# Transconductance.net
KiCad netlist of a schematic drawn in Altium Designer
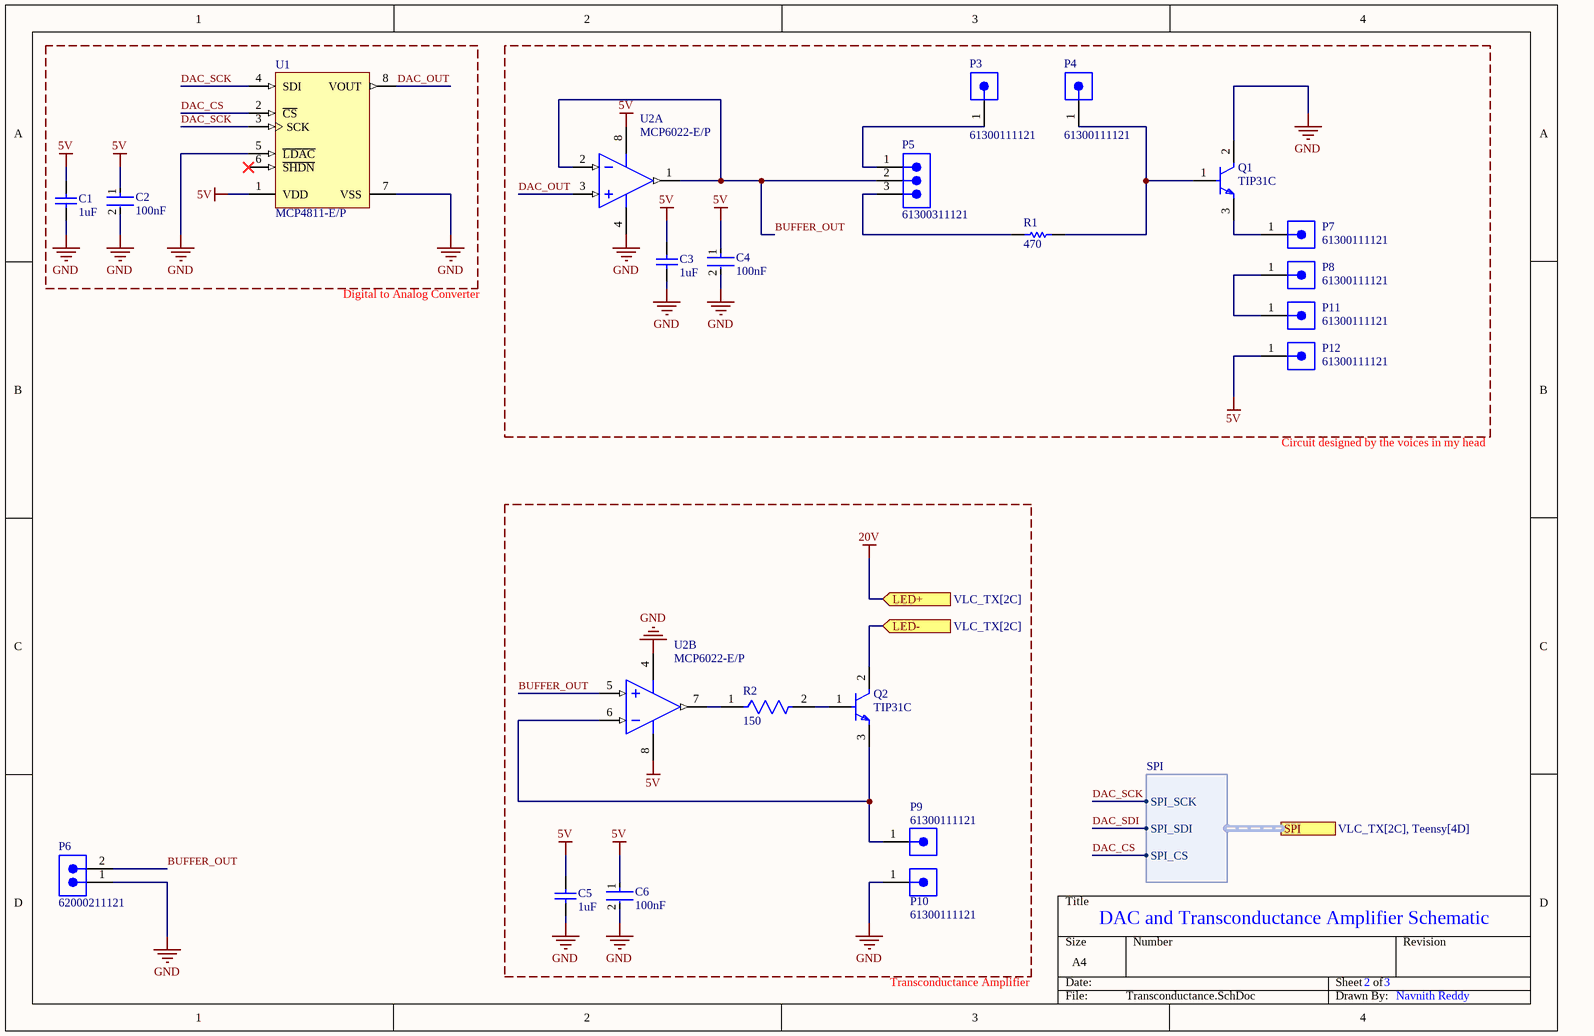
[diagram p0: Transconductance.SchDoc]

(export (version "E")
  (design (tool "Eeschema 10.0.6"))
  (components
    (comp (ref "C1")
      (value "1uF")
      (footprint "CAPC2013X145X50LL20T25")
      (fields (field (name "MANUFACTURER") "Kemet") (field (name "PART NUMBER") "C0805C105K4PACTU"))
      (libsource (lib "Altium Content Vault") (part "CAP"))
    )
    (comp (ref "C2")
      (value "100nF")
      (footprint "FP-C0805C-DN-MFG")
      (description "CAP CER 0.1UF 16V X7R 0805")
      (fields
        (field (name "OCTOPART") "https://octopart.com/c0805c104k4ractu-kemet-92155")
        (field (name "TOLERANCE") "0.1")
      )
      (libsource (lib "Altium Content Vault") (part "b4654b650e69147ec39a6b967a45e02"))
    )
    (comp (ref "C3")
      (value "1uF")
      (footprint "CAPC2013X145X50LL20T25")
      (fields (field (name "MANUFACTURER") "Kemet") (field (name "PART NUMBER") "C0805C105K4PACTU"))
      (libsource (lib "Altium Content Vault") (part "CAP"))
    )
    (comp (ref "C4")
      (value "100nF")
      (footprint "FP-C0805C-DN-MFG")
      (description "CAP CER 0.1UF 16V X7R 0805")
      (fields
        (field (name "OCTOPART") "https://octopart.com/c0805c104k4ractu-kemet-92155")
        (field (name "TOLERANCE") "0.1")
      )
      (libsource (lib "Altium Content Vault") (part "b4654b650e69147ec39a6b967a45e02"))
    )
    (comp (ref "C5")
      (value "1uF")
      (footprint "CAPC2013X145X50LL20T25")
      (fields (field (name "MANUFACTURER") "Kemet") (field (name "PART NUMBER") "C0805C105K4PACTU"))
      (libsource (lib "Altium Content Vault") (part "CAP"))
    )
    (comp (ref "C6")
      (value "100nF")
      (footprint "FP-C0805C-DN-MFG")
      (description "CAP CER 0.1UF 16V X7R 0805")
      (fields
        (field (name "OCTOPART") "https://octopart.com/c0805c104k4ractu-kemet-92155")
        (field (name "TOLERANCE") "0.1")
      )
      (libsource (lib "Altium Content Vault") (part "b4654b650e69147ec39a6b967a45e02"))
    )
    (comp (ref "P3")
      (value "61300111121")
      (footprint "61300111121")
      (libsource (lib "Altium Content Vault") (part "Header_Male_1R_01P"))
    )
    (comp (ref "P4")
      (value "61300111121")
      (footprint "61300111121")
      (libsource (lib "Altium Content Vault") (part "Header_Male_1R_01P"))
    )
    (comp (ref "P5")
      (value "61300311121")
      (footprint "61300311121")
      (libsource (lib "Altium Content Vault") (part "Header_Male_1R_03P"))
    )
    (comp (ref "P6")
      (value "62000211121")
      (footprint "62000211121")
      (libsource (lib "Altium Content Vault") (part "Header_Male_1R_02P"))
    )
    (comp (ref "P7")
      (value "61300111121")
      (footprint "61300111121")
      (libsource (lib "Altium Content Vault") (part "Header_Male_1R_01P"))
    )
    (comp (ref "P8")
      (value "61300111121")
      (footprint "61300111121")
      (libsource (lib "Altium Content Vault") (part "Header_Male_1R_01P"))
    )
    (comp (ref "P9")
      (value "61300111121")
      (footprint "61300111121")
      (libsource (lib "Altium Content Vault") (part "Header_Male_1R_01P"))
    )
    (comp (ref "P10")
      (value "61300111121")
      (footprint "61300111121")
      (libsource (lib "Altium Content Vault") (part "Header_Male_1R_01P"))
    )
    (comp (ref "P11")
      (value "61300111121")
      (footprint "61300111121")
      (libsource (lib "Altium Content Vault") (part "Header_Male_1R_01P"))
    )
    (comp (ref "P12")
      (value "61300111121")
      (footprint "61300111121")
      (libsource (lib "Altium Content Vault") (part "Header_Male_1R_01P"))
    )
    (comp (ref "Q1")
      (value "TIP31C")
      (footprint "FP-TO-220-P0A0015988-MFG")
      (description "TRANS NPN 100V 3A TO-220")
      (fields
        (field (name "OCTOPART") "https://octopart.com/tip31c-stmicroelectronics-15555")
        (field (name "MANUFACTURER") "STMicroelectronics")
      )
      (libsource (lib "Altium Content Vault") (part "1c57d9dae74fe2702546667b0e849db"))
    )
    (comp (ref "Q2")
      (value "TIP31C")
      (footprint "FP-TO-220-P0A0015988-MFG")
      (description "TRANS NPN 100V 3A TO-220")
      (fields
        (field (name "OCTOPART") "https://octopart.com/tip31c-stmicroelectronics-15555")
        (field (name "MANUFACTURER") "STMicroelectronics")
      )
      (libsource (lib "Altium Content Vault") (part "1c57d9dae74fe2702546667b0e849db"))
    )
    (comp (ref "R1")
      (value "470")
      (footprint "RESC2013X50X30LL20T20")
      (fields (field (name "MANUFACTURER") "Vishay Dale") (field (name "PART NUMBER") "CRCW0805470RFKEA"))
      (libsource (lib "Altium Content Vault") (part "RES"))
    )
    (comp (ref "R2")
      (value "150")
      (footprint "FP-CRCW0805-e3-IPC_A")
      (description "RES Thick Film, 150Ω, 5%, 0.125W, 200ppm/°C, 0805")
      (fields (field (name "TOLERANCE") "5%"))
      (libsource (lib "Altium Content Vault") (part "1029c3af85768c4190bb7ad29bc67b5"))
    )
    (comp (ref "U1")
      (value "MCP4811-E/P")
      (footprint "PDIP300-P8")
      (description "10-Bit DACs with Internal VREF and SPI Interface, 8-Pin PDIP, Extended Temperature")
      (libsource (lib "Altium Content Vault") (part "CON-DAC-MCP4821-8"))
    )
    (comp (ref "U2")
      (value "MCP6022-E/P")
      (footprint "PDIP300-P8")
      (description "None")
      (libsource (lib "Altium Content Vault") (part "AMP-OPA-MCP6022-IL8"))
    )
  )
  (nets
    (net (code "2") (name "/BUFFER_OUT") (class "Default")
      (node (ref "P5") (pin "2") (pinfunction "2_2") (pintype "passive"))
      (node (ref "P6") (pin "2") (pinfunction "2_2") (pintype "passive"))
      (node (ref "U2") (pin "1") (pinfunction "VOUTA_1") (pintype "output"))
      (node (ref "U2") (pin "2") (pinfunction "VINA-_2") (pintype "input"))
      (node (ref "U2") (pin "5") (pinfunction "VINB+_5") (pintype "input"))
    )
    (net (code "3") (name "/DAC_CS") (class "Default")
      (node (ref "U1") (pin "2") (pinfunction "~{CS}_2") (pintype "input"))
    )
    (net (code "4") (name "/DAC_OUT") (class "Default")
      (node (ref "U1") (pin "8") (pinfunction "VOUT_8") (pintype "output"))
      (node (ref "U2") (pin "3") (pinfunction "VINA+_3") (pintype "input"))
    )
    (net (code "5") (name "/DAC_SCK") (class "Default")
      (node (ref "U1") (pin "3") (pinfunction "SCK_3") (pintype "input"))
      (node (ref "U1") (pin "4") (pinfunction "SDI_4") (pintype "input"))
    )
    (net (code "7") (name "/LED-") (class "Default")
      (node (ref "Q2") (pin "2") (pinfunction "C_2") (pintype "passive"))
    )
    (net (code "9") (name "5V") (class "Default")
      (node (ref "C1") (pin "2") (pinfunction "2_2") (pintype "passive"))
      (node (ref "C2") (pin "1") (pinfunction "1_1") (pintype "passive"))
      (node (ref "C3") (pin "2") (pinfunction "2_2") (pintype "passive"))
      (node (ref "C4") (pin "1") (pinfunction "1_1") (pintype "passive"))
      (node (ref "C5") (pin "2") (pinfunction "2_2") (pintype "passive"))
      (node (ref "C6") (pin "1") (pinfunction "1_1") (pintype "passive"))
      (node (ref "P12") (pin "1") (pinfunction "1_1") (pintype "passive"))
      (node (ref "U1") (pin "1") (pinfunction "VDD_1") (pintype "power_in"))
      (node (ref "U2") (pin "8") (pinfunction "VDD_8") (pintype "power_in"))
    )
    (net (code "11") (name "GND") (class "Default")
      (node (ref "C1") (pin "1") (pinfunction "1_1") (pintype "passive"))
      (node (ref "C2") (pin "2") (pinfunction "2_2") (pintype "passive"))
      (node (ref "C3") (pin "1") (pinfunction "1_1") (pintype "passive"))
      (node (ref "C4") (pin "2") (pinfunction "2_2") (pintype "passive"))
      (node (ref "C5") (pin "1") (pinfunction "1_1") (pintype "passive"))
      (node (ref "C6") (pin "2") (pinfunction "2_2") (pintype "passive"))
      (node (ref "P10") (pin "1") (pinfunction "1_1") (pintype "passive"))
      (node (ref "P6") (pin "1") (pinfunction "1_1") (pintype "passive"))
      (node (ref "Q1") (pin "2") (pinfunction "C_2") (pintype "passive"))
      (node (ref "U1") (pin "5") (pinfunction "~{LDAC}_5") (pintype "input"))
      (node (ref "U1") (pin "7") (pinfunction "VSS_7") (pintype "power_in"))
      (node (ref "U2") (pin "4") (pinfunction "VSS_4") (pintype "power_in"))
    )
    (net (code "12") (name "Net-(P3-Pad1)") (class "Default")
      (node (ref "P3") (pin "1") (pinfunction "1_1") (pintype "passive"))
      (node (ref "P5") (pin "1") (pinfunction "1_1") (pintype "passive"))
    )
    (net (code "13") (name "Net-(P5-Pad3)") (class "Default")
      (node (ref "P5") (pin "3") (pinfunction "3_3") (pintype "passive"))
      (node (ref "R1") (pin "1") (pinfunction "1_1") (pintype "passive"))
    )
    (net (code "14") (name "Net-(P11-Pad1)") (class "Default")
      (node (ref "P11") (pin "1") (pinfunction "1_1") (pintype "passive"))
      (node (ref "P8") (pin "1") (pinfunction "1_1") (pintype "passive"))
    )
    (net (code "15") (name "Net-(Q1-B)") (class "Default")
      (node (ref "P4") (pin "1") (pinfunction "1_1") (pintype "passive"))
      (node (ref "Q1") (pin "1") (pinfunction "B_1") (pintype "passive"))
      (node (ref "R1") (pin "2") (pinfunction "2_2") (pintype "passive"))
    )
    (net (code "16") (name "Net-(Q1-E)") (class "Default")
      (node (ref "P7") (pin "1") (pinfunction "1_1") (pintype "passive"))
      (node (ref "Q1") (pin "3") (pinfunction "E_3") (pintype "passive"))
    )
    (net (code "17") (name "Net-(Q2-B)") (class "Default")
      (node (ref "Q2") (pin "1") (pinfunction "B_1") (pintype "passive"))
      (node (ref "R2") (pin "2") (pinfunction "2_2") (pintype "passive"))
    )
    (net (code "18") (name "Net-(Q2-E)") (class "Default")
      (node (ref "P9") (pin "1") (pinfunction "1_1") (pintype "passive"))
      (node (ref "Q2") (pin "3") (pinfunction "E_3") (pintype "passive"))
      (node (ref "U2") (pin "6") (pinfunction "VINB-_6") (pintype "input"))
    )
    (net (code "19") (name "Net-(U2B-VOUTB)") (class "Default")
      (node (ref "R2") (pin "1") (pinfunction "1_1") (pintype "passive"))
      (node (ref "U2") (pin "7") (pinfunction "VOUTB_7") (pintype "output"))
    )
    (net (code "20") (name "unconnected-(U1-~{SHDN}-Pad6)") (class "Default")
      (node (ref "U1") (pin "6") (pinfunction "~{SHDN}_6") (pintype "input+no_connect"))
    )
  )
)
